# 1-Schematic_Plawas-m.net
KiCad netlist of a schematic drawn in EasyEDA
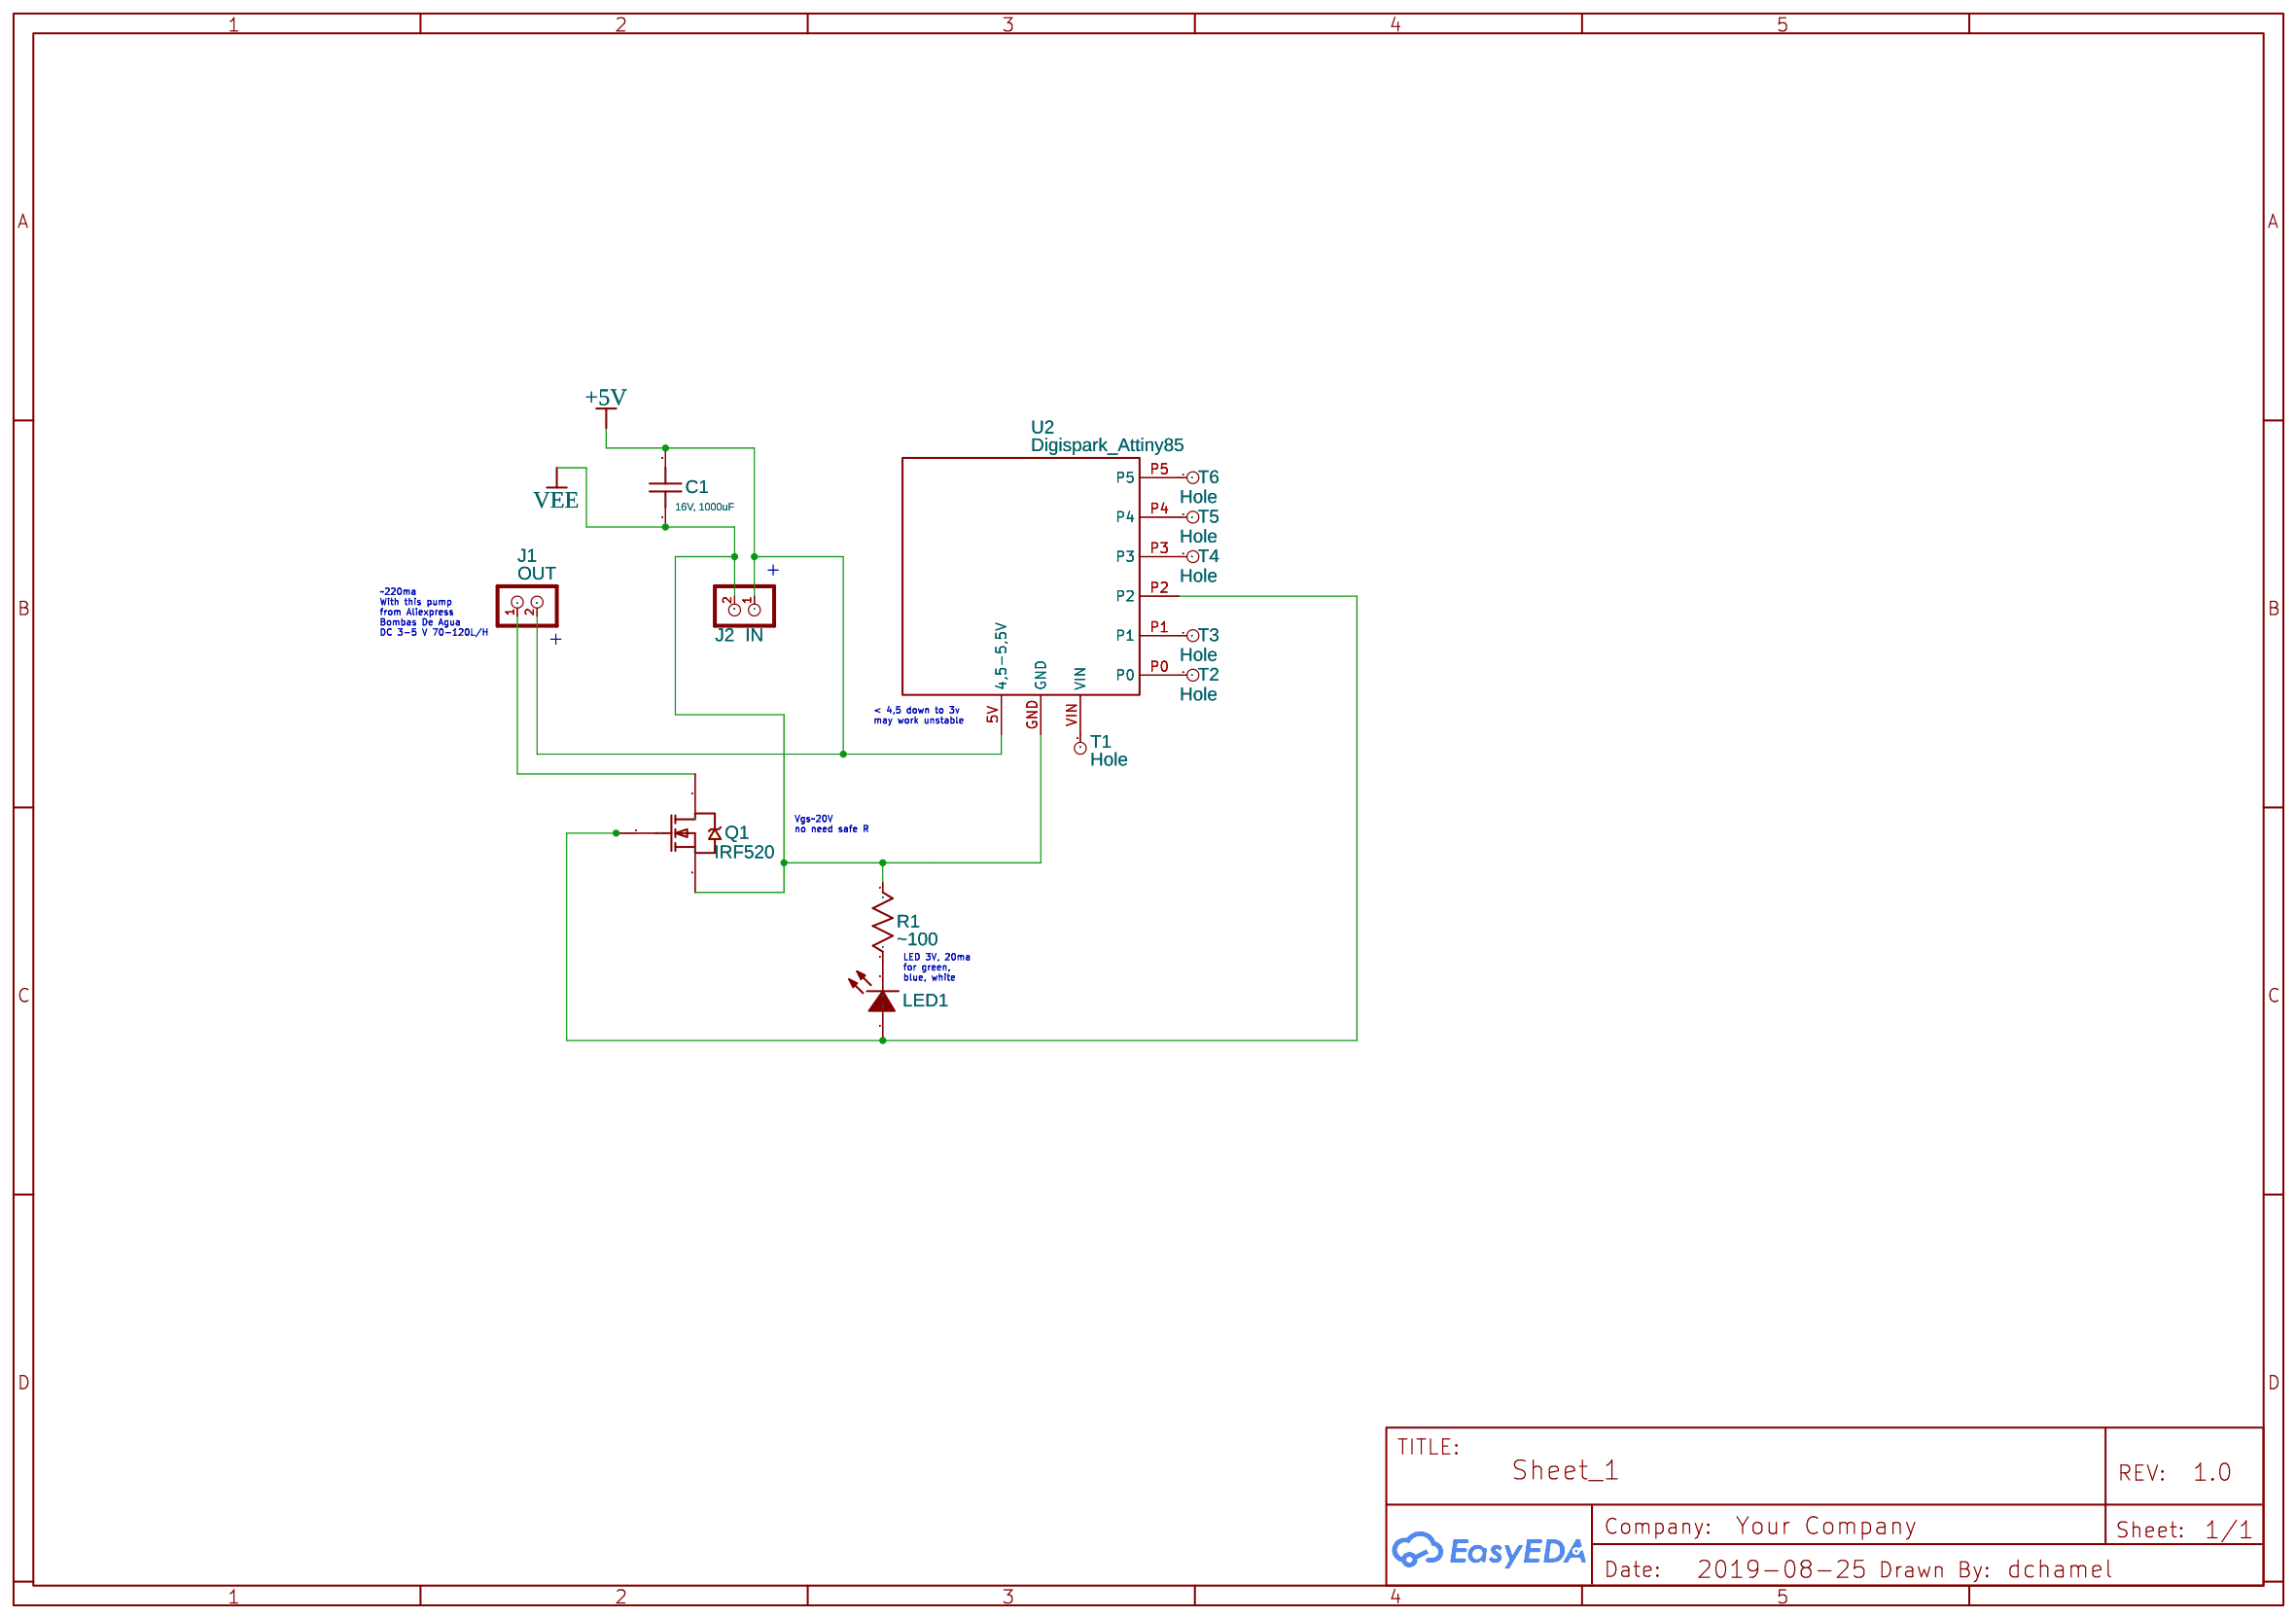
[diagram p0: schematic sheet]

(export (version "E")
  (design (tool "Eeschema 10.0.6"))
  (components
    (comp (ref "C1") (value "16V, 1000uF") (libsource (lib "") (part "Cap_RAD-0.1_US")))
    (comp (ref "J1") (value "OUT") (libsource (lib "") (part "CON_TERMINAL_BLOCK_02-5MM")))
    (comp (ref "J2") (value "IN") (libsource (lib "") (part "CON_TERMINAL_BLOCK_02-5MM_1")))
    (comp (ref "LED1")
      (value "204-10SURD/S530-A3")
      (fields (field (name "BOM_Supplier Part") "C99772"))
      (libsource (lib "") (part "204-10SURD/S530-A3"))
    )
    (comp (ref "Q1") (value "IRF520") (libsource (lib "") (part "IRF520")))
    (comp (ref "R1") (value "100") (libsource (lib "") (part "Res_AXIAL-0.3(1/8W)_US")))
    (comp (ref "T1") (value "Hole") (libsource (lib "") (part "PAD_TERMINAL_1")))
    (comp (ref "T2") (value "Hole") (libsource (lib "") (part "PAD_TERMINAL")))
    (comp (ref "T3") (value "Hole") (libsource (lib "") (part "PAD_TERMINAL")))
    (comp (ref "T4") (value "Hole") (libsource (lib "") (part "PAD_TERMINAL")))
    (comp (ref "T5") (value "Hole") (libsource (lib "") (part "PAD_TERMINAL")))
    (comp (ref "T6") (value "Hole") (libsource (lib "") (part "PAD_TERMINAL")))
    (comp (ref "U2") (value "Digispark_Attiny85") (libsource (lib "") (part "Unknown_470_315")))
  )
  (nets
    (net (code "1") (name "+5V") (class "Default")
      (node (ref "C1") (pin "2") (pinfunction "2_2") (pintype "unspecified"))
      (node (ref "J1") (pin "2") (pinfunction "2_2") (pintype "unspecified"))
      (node (ref "J2") (pin "1") (pinfunction "1_1") (pintype "unspecified"))
      (node (ref "U2") (pin "5V") (pinfunction "4,5-5,5V_5V") (pintype "unspecified"))
    )
    (net (code "2") (name "Net-(LED1-A)") (class "Default")
      (node (ref "LED1") (pin "1") (pinfunction "A_1") (pintype "unspecified"))
      (node (ref "Q1") (pin "1") (pinfunction "G_1") (pintype "unspecified"))
      (node (ref "U2") (pin "P2") (pinfunction "P2_P2") (pintype "unspecified"))
    )
    (net (code "3") (name "Net-(LED1-K)") (class "Default")
      (node (ref "LED1") (pin "2") (pinfunction "K_2") (pintype "unspecified"))
      (node (ref "R1") (pin "1") (pinfunction "1_1") (pintype "unspecified"))
    )
    (net (code "4") (name "Net-(Q1-D)") (class "Default")
      (node (ref "J1") (pin "1") (pinfunction "1_1") (pintype "unspecified"))
      (node (ref "Q1") (pin "2") (pinfunction "D_2") (pintype "unspecified"))
    )
    (net (code "5") (name "Net-(T1-PadP)") (class "Default")
      (node (ref "T1") (pin "P") (pinfunction "P_P") (pintype "unspecified"))
      (node (ref "U2") (pin "VIN") (pinfunction "VIN_VIN") (pintype "unspecified"))
    )
    (net (code "6") (name "Net-(T2-PadP)") (class "Default")
      (node (ref "T2") (pin "P") (pinfunction "P_P") (pintype "unspecified"))
      (node (ref "U2") (pin "P0") (pinfunction "P0_P0") (pintype "unspecified"))
    )
    (net (code "7") (name "Net-(T3-PadP)") (class "Default")
      (node (ref "T3") (pin "P") (pinfunction "P_P") (pintype "unspecified"))
      (node (ref "U2") (pin "P1") (pinfunction "P1_P1") (pintype "unspecified"))
    )
    (net (code "8") (name "Net-(T4-PadP)") (class "Default")
      (node (ref "T4") (pin "P") (pinfunction "P_P") (pintype "unspecified"))
      (node (ref "U2") (pin "P3") (pinfunction "P3_P3") (pintype "unspecified"))
    )
    (net (code "9") (name "Net-(T5-PadP)") (class "Default")
      (node (ref "T5") (pin "P") (pinfunction "P_P") (pintype "unspecified"))
      (node (ref "U2") (pin "P4") (pinfunction "P4_P4") (pintype "unspecified"))
    )
    (net (code "10") (name "Net-(T6-PadP)") (class "Default")
      (node (ref "T6") (pin "P") (pinfunction "P_P") (pintype "unspecified"))
      (node (ref "U2") (pin "P5") (pinfunction "P5_P5") (pintype "unspecified"))
    )
    (net (code "11") (name "VEE") (class "Default")
      (node (ref "C1") (pin "1") (pinfunction "1_1") (pintype "unspecified"))
      (node (ref "J2") (pin "2") (pinfunction "2_2") (pintype "unspecified"))
      (node (ref "Q1") (pin "3") (pinfunction "S_3") (pintype "unspecified"))
      (node (ref "R1") (pin "2") (pinfunction "2_2") (pintype "unspecified"))
      (node (ref "U2") (pin "GND") (pinfunction "GND_GND") (pintype "unspecified"))
    )
  )
)
